# CAN.net
KiCad netlist of a schematic drawn in Altium Designer
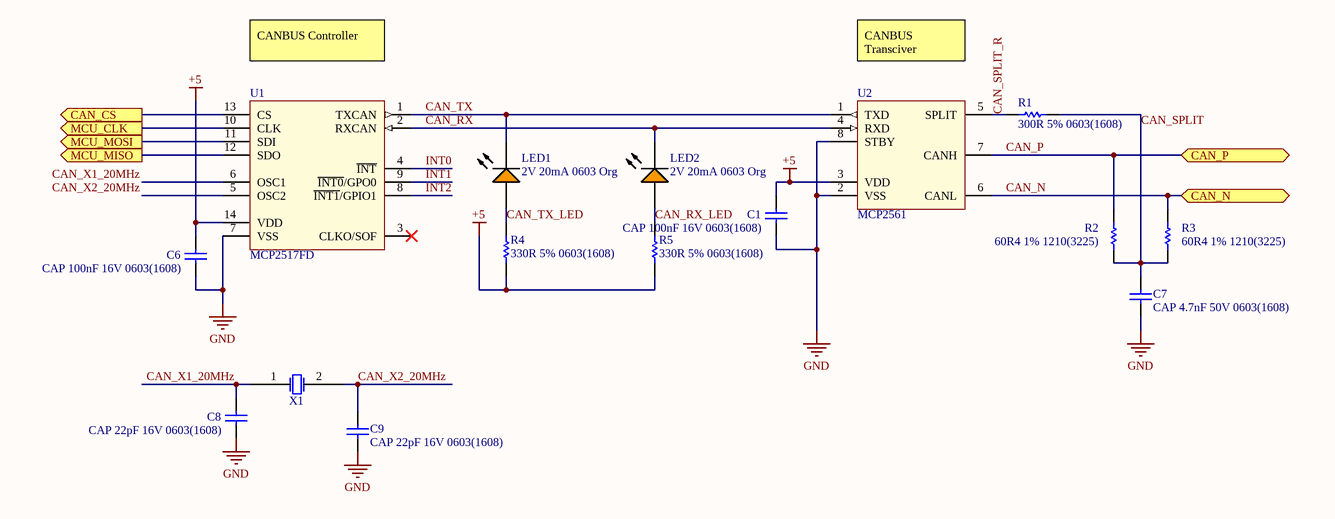
[diagram p0: CAN.SchDoc]

(export (version "E")
  (design (tool "Eeschema 10.0.6"))
  (components
    (comp (ref "C1")
      (value "CAP 100nF 16V 0603(1608)")
      (footprint "CAPC0603(1608)100_N")
      (description "CAP 100nF 16V ±10% 0603 (1608 Metric) Thickness 1mm SMD")
      (fields (field (name "TOLERANCE") "Â±10%"))
      (libsource (lib "Altium Content Vault") (part "CAP"))
    )
    (comp (ref "C6")
      (value "CAP 100nF 16V 0603(1608)")
      (footprint "CAPC0603(1608)100_N")
      (description "CAP 100nF 16V ±10% 0603 (1608 Metric) Thickness 1mm SMD")
      (fields (field (name "TOLERANCE") "Â±10%"))
      (libsource (lib "Altium Content Vault") (part "CAP"))
    )
    (comp (ref "C7")
      (value "CAP 4.7nF 50V 0603(1608)")
      (footprint "CAPC0603(1608)100_M")
      (description "CAP 4.7nF 50V ±5% 0603 (1608 Metric) Thickness 1mm SMD")
      (fields (field (name "TOLERANCE") "Â±5%"))
      (libsource (lib "Altium Content Vault") (part "CAP"))
    )
    (comp (ref "C8")
      (value "CAP 22pF 16V 0603(1608)")
      (footprint "CAPC0603(1608)100_N")
      (description "CAP 22pF 16V ±5% 0603 (1608 Metric) Thickness 1mm SMD")
      (fields (field (name "TOLERANCE") "Â±5%"))
      (libsource (lib "Altium Content Vault") (part "CAP"))
    )
    (comp (ref "C9")
      (value "CAP 22pF 16V 0603(1608)")
      (footprint "CAPC0603(1608)100_N")
      (description "CAP 22pF 16V ±5% 0603 (1608 Metric) Thickness 1mm SMD")
      (fields (field (name "TOLERANCE") "Â±5%"))
      (libsource (lib "Altium Content Vault") (part "CAP"))
    )
    (comp (ref "LED1")
      (value "2V 20mA 0603 Org")
      (footprint "KING-LED0603-25-ORANGE_V")
      (description "LED, SMT, 0603(1608), 0.25mm Tthickness, Super Bright Orange")
      (fields (field (name "PARTNUMBER") "APG1608SEKC/T"))
      (libsource (lib "Altium Content Vault") (part "KING-LED_ORANGE_A1K2-2"))
    )
    (comp (ref "LED2")
      (value "2V 20mA 0603 Org")
      (footprint "KING-LED0603-25-ORANGE_V")
      (description "LED, SMT, 0603(1608), 0.25mm Tthickness, Super Bright Orange")
      (fields (field (name "PARTNUMBER") "APG1608SEKC/T"))
      (libsource (lib "Altium Content Vault") (part "KING-LED_ORANGE_A1K2-2"))
    )
    (comp (ref "R1")
      (value "300R 5% 0603(1608)")
      (footprint "RESC0603(1608)_N")
      (description "300R 0.1W 5% 0603 (1608 Metric)  SMD")
      (fields (field (name "TOLERANCE") "5 %") (field (name "POWER") "0.1 W"))
      (libsource (lib "Altium Content Vault") (part "RES"))
    )
    (comp (ref "R2")
      (value "60R4 1% 1210(3225)")
      (footprint "RESC1210(3225)_L")
      (description "60R4 0.5W 1% 1210 (3225 Metric)  SMD")
      (fields (field (name "TOLERANCE") "1 %") (field (name "POWER") "0.5 W"))
      (libsource (lib "Altium Content Vault") (part "RES"))
    )
    (comp (ref "R3")
      (value "60R4 1% 1210(3225)")
      (footprint "RESC1210(3225)_L")
      (description "60R4 0.5W 1% 1210 (3225 Metric)  SMD")
      (fields (field (name "TOLERANCE") "1 %") (field (name "POWER") "0.5 W"))
      (libsource (lib "Altium Content Vault") (part "RES"))
    )
    (comp (ref "R4")
      (value "330R 5% 0603(1608)")
      (footprint "RESC0603(1608)_L")
      (description "330R 0.1W 5% 0603 (1608 Metric)  SMD")
      (fields (field (name "TOLERANCE") "5 %") (field (name "POWER") "0.1 W"))
      (libsource (lib "Altium Content Vault") (part "RES"))
    )
    (comp (ref "R5")
      (value "330R 5% 0603(1608)")
      (footprint "RESC0603(1608)_L")
      (description "330R 0.1W 5% 0603 (1608 Metric)  SMD")
      (fields (field (name "TOLERANCE") "5 %") (field (name "POWER") "0.1 W"))
      (libsource (lib "Altium Content Vault") (part "RES"))
    )
    (comp (ref "U1")
      (value "MCP2517FD")
      (footprint "MCP2517FD SOIC")
      (libsource (lib "QUTMS_CANLibrary") (part "MCP2517FD"))
    )
    (comp (ref "U2")
      (value "MCP2561")
      (footprint "MCP2561 SOIC")
      (libsource (lib "QUTMS_CANLibrary") (part "MCP2561"))
    )
    (comp (ref "X1")
      (value "Crystal 20MHz")
      (footprint "Crystal 20MHz")
      (libsource (lib "QUTMS_CrystalLibrary") (part "Crystal 20MHz"))
    )
  )
  (nets
    (net (code "1") (name "+5") (class "Default")
      (node (ref "C1") (pin "2") (pinfunction "2_2") (pintype "passive"))
      (node (ref "C6") (pin "2") (pinfunction "2_2") (pintype "passive"))
      (node (ref "R4") (pin "2") (pinfunction "2_2") (pintype "passive"))
      (node (ref "R5") (pin "2") (pinfunction "2_2") (pintype "passive"))
      (node (ref "U1") (pin "14") (pinfunction "VDD_14") (pintype "passive"))
      (node (ref "U2") (pin "3") (pinfunction "VDD_3") (pintype "passive"))
    )
    (net (code "2") (name "/CAN_CS") (class "Default")
      (node (ref "U1") (pin "13") (pinfunction "CS_13") (pintype "passive"))
    )
    (net (code "3") (name "/CAN_N") (class "Default")
      (node (ref "R3") (pin "2") (pinfunction "2_2") (pintype "passive"))
      (node (ref "U2") (pin "6") (pinfunction "CANL_6") (pintype "passive"))
    )
    (net (code "4") (name "/CAN_P") (class "Default")
      (node (ref "R2") (pin "2") (pinfunction "2_2") (pintype "passive"))
      (node (ref "U2") (pin "7") (pinfunction "CANH_7") (pintype "passive"))
    )
    (net (code "5") (name "/CAN_RX") (class "Default")
      (node (ref "LED2") (pin "2") (pinfunction "K_2") (pintype "passive"))
      (node (ref "U1") (pin "2") (pinfunction "RXCAN_2") (pintype "input"))
      (node (ref "U2") (pin "4") (pinfunction "RXD_4") (pintype "input"))
    )
    (net (code "6") (name "/CAN_RX_LED") (class "Default")
      (node (ref "LED2") (pin "1") (pinfunction "A_1") (pintype "passive"))
      (node (ref "R5") (pin "1") (pinfunction "1_1") (pintype "passive"))
    )
    (net (code "7") (name "/CAN_SPLIT") (class "Default")
      (node (ref "C7") (pin "2") (pinfunction "2_2") (pintype "passive"))
      (node (ref "R1") (pin "2") (pinfunction "2_2") (pintype "passive"))
      (node (ref "R2") (pin "1") (pinfunction "1_1") (pintype "passive"))
      (node (ref "R3") (pin "1") (pinfunction "1_1") (pintype "passive"))
    )
    (net (code "8") (name "/CAN_SPLIT_R") (class "Default")
      (node (ref "R1") (pin "1") (pinfunction "1_1") (pintype "passive"))
      (node (ref "U2") (pin "5") (pinfunction "SPLIT_5") (pintype "passive"))
    )
    (net (code "9") (name "/CAN_TX") (class "Default")
      (node (ref "LED1") (pin "2") (pinfunction "K_2") (pintype "passive"))
      (node (ref "U1") (pin "1") (pinfunction "TXCAN_1") (pintype "output"))
      (node (ref "U2") (pin "1") (pinfunction "TXD_1") (pintype "output"))
    )
    (net (code "10") (name "/CAN_TX_LED") (class "Default")
      (node (ref "LED1") (pin "1") (pinfunction "A_1") (pintype "passive"))
      (node (ref "R4") (pin "1") (pinfunction "1_1") (pintype "passive"))
    )
    (net (code "11") (name "/CAN_X1_20MHz") (class "Default")
      (node (ref "C8") (pin "2") (pinfunction "2_2") (pintype "passive"))
      (node (ref "U1") (pin "6") (pinfunction "OSC1_6") (pintype "passive"))
      (node (ref "X1") (pin "1") (pintype "passive"))
    )
    (net (code "12") (name "/CAN_X2_20MHz") (class "Default")
      (node (ref "C9") (pin "1") (pinfunction "1_1") (pintype "passive"))
      (node (ref "U1") (pin "5") (pinfunction "OSC2_5") (pintype "passive"))
      (node (ref "X1") (pin "2") (pintype "passive"))
    )
    (net (code "13") (name "/INT0") (class "Default")
      (node (ref "U1") (pin "4") (pinfunction "~{INT}_4") (pintype "passive"))
    )
    (net (code "14") (name "/INT1") (class "Default")
      (node (ref "U1") (pin "9") (pinfunction "~{INT0}/GPO0_9") (pintype "passive"))
    )
    (net (code "15") (name "/INT2") (class "Default")
      (node (ref "U1") (pin "8") (pinfunction "~{INT1}/GPIO1_8") (pintype "passive"))
    )
    (net (code "16") (name "/MCU_CLK") (class "Default")
      (node (ref "U1") (pin "10") (pinfunction "CLK_10") (pintype "passive"))
    )
    (net (code "17") (name "/MCU_MISO") (class "Default")
      (node (ref "U1") (pin "12") (pinfunction "SDO_12") (pintype "passive"))
    )
    (net (code "18") (name "/MCU_MOSI") (class "Default")
      (node (ref "U1") (pin "11") (pinfunction "SDI_11") (pintype "passive"))
    )
    (net (code "19") (name "GND") (class "Default")
      (node (ref "C1") (pin "1") (pinfunction "1_1") (pintype "passive"))
      (node (ref "C6") (pin "1") (pinfunction "1_1") (pintype "passive"))
      (node (ref "C7") (pin "1") (pinfunction "1_1") (pintype "passive"))
      (node (ref "C8") (pin "1") (pinfunction "1_1") (pintype "passive"))
      (node (ref "C9") (pin "2") (pinfunction "2_2") (pintype "passive"))
      (node (ref "U1") (pin "7") (pinfunction "VSS_7") (pintype "passive"))
      (node (ref "U2") (pin "2") (pinfunction "VSS_2") (pintype "passive"))
      (node (ref "U2") (pin "8") (pinfunction "STBY_8") (pintype "passive"))
    )
    (net (code "20") (name "unconnected-(U1-CLKO{slash}SOF-Pad3)") (class "Default")
      (node (ref "U1") (pin "3") (pinfunction "CLKO/SOF_3") (pintype "passive+no_connect"))
    )
  )
)
